# project2.net
KiCad netlist of a schematic drawn in EAGLE
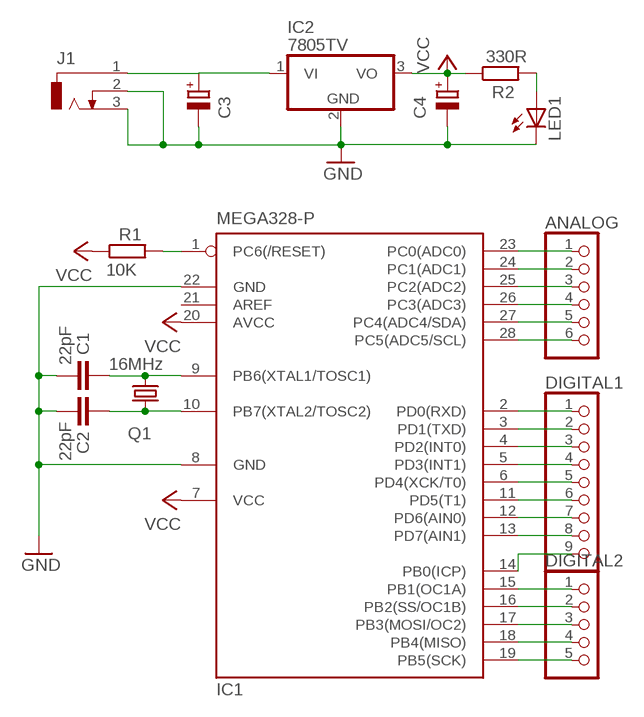
[diagram p0: schematic, sheet 1]

(export (version "E")
  (design (tool "Eeschema 10.0.6"))
  (components
    (comp (ref "ANALOG")
      (value "PINHD-1X6")
      (footprint "eagle-import:1X06")
      (libsource (lib "eagle-import") (part "PINHD-1X6"))
    )
    (comp (ref "C1")
      (value "22pF")
      (footprint "eagle-import:C025-024X044")
      (libsource (lib "eagle-import") (part "C-EU025-024X044"))
    )
    (comp (ref "C2")
      (value "22pF")
      (footprint "eagle-import:C025-024X044")
      (libsource (lib "eagle-import") (part "C-EU025-024X044"))
    )
    (comp (ref "C3")
      (value "CPOL-EUE2.5-6")
      (footprint "eagle-import:E2,5-6")
      (libsource (lib "eagle-import") (part "CPOL-EUE2.5-6"))
    )
    (comp (ref "C4")
      (value "CPOL-EUE2.5-6")
      (footprint "eagle-import:E2,5-6")
      (libsource (lib "eagle-import") (part "CPOL-EUE2.5-6"))
    )
    (comp (ref "DIGITAL1")
      (value "PINHD-1X9")
      (footprint "eagle-import:1X09")
      (libsource (lib "eagle-import") (part "PINHD-1X9"))
    )
    (comp (ref "DIGITAL2")
      (value "PINHD-1X5")
      (footprint "eagle-import:1X05")
      (libsource (lib "eagle-import") (part "PINHD-1X5"))
    )
    (comp (ref "IC1")
      (value "MEGA328-P")
      (footprint "eagle-import:DIL28-3")
      (libsource (lib "eagle-import") (part "MEGA8-P"))
    )
    (comp (ref "IC2")
      (value "7805TV")
      (footprint "eagle-import:TO220V")
      (libsource (lib "eagle-import") (part "78TV05"))
    )
    (comp (ref "J1")
      (value "DCJ0303")
      (footprint "eagle-import:DCJ0303")
      (libsource (lib "eagle-import") (part "DCJ0303"))
    )
    (comp (ref "LED1")
      (value "LED3MM")
      (footprint "eagle-import:LED3MM")
      (libsource (lib "eagle-import") (part "LED3MM"))
    )
    (comp (ref "Q1")
      (value "16MHz")
      (footprint "eagle-import:HC49U70")
      (libsource (lib "eagle-import") (part "CRYSTALHC49U70"))
    )
    (comp (ref "R1")
      (value "10K")
      (footprint "eagle-import:0207_10")
      (libsource (lib "eagle-import") (part "R-EU_0207/10"))
    )
    (comp (ref "R2")
      (value "330R")
      (footprint "eagle-import:0207_10")
      (libsource (lib "eagle-import") (part "R-EU_0207/10"))
    )
  )
  (nets
    (net (code "1") (name "GND") (class "Default")
      (node (ref "C1") (pin "2") (pinfunction "2_2") (pintype "passive"))
      (node (ref "C2") (pin "2") (pinfunction "2_2") (pintype "passive"))
      (node (ref "C3") (pin "-") (pinfunction "-_-") (pintype "passive"))
      (node (ref "C4") (pin "-") (pinfunction "-_-") (pintype "passive"))
      (node (ref "IC1") (pin "22") (pinfunction "GND_22") (pintype "power_in"))
      (node (ref "IC1") (pin "8") (pinfunction "GND_8") (pintype "power_in"))
      (node (ref "IC2") (pin "2") (pinfunction "GND_2") (pintype "passive"))
      (node (ref "J1") (pin "2") (pinfunction "2_2") (pintype "passive"))
      (node (ref "J1") (pin "3") (pinfunction "3_3") (pintype "passive"))
      (node (ref "LED1") (pin "K") (pinfunction "C_K") (pintype "passive"))
    )
    (net (code "2") (name "Net-(IC1-PB0(ICP))") (class "Default")
      (node (ref "DIGITAL1") (pin "9") (pinfunction "9_9") (pintype "passive"))
      (node (ref "IC1") (pin "14") (pinfunction "PB0(ICP)_14") (pintype "bidirectional"))
    )
    (net (code "3") (name "Net-(IC1-PB1(OC1A))") (class "Default")
      (node (ref "DIGITAL2") (pin "1") (pinfunction "1_1") (pintype "passive"))
      (node (ref "IC1") (pin "15") (pinfunction "PB1(OC1A)_15") (pintype "bidirectional"))
    )
    (net (code "4") (name "Net-(IC1-PB2(SS{slash}OC1B))") (class "Default")
      (node (ref "DIGITAL2") (pin "2") (pinfunction "2_2") (pintype "passive"))
      (node (ref "IC1") (pin "16") (pinfunction "PB2(SS/OC1B)_16") (pintype "bidirectional"))
    )
    (net (code "5") (name "Net-(IC1-PB3(MOSI{slash}OC2))") (class "Default")
      (node (ref "DIGITAL2") (pin "3") (pinfunction "3_3") (pintype "passive"))
      (node (ref "IC1") (pin "17") (pinfunction "PB3(MOSI/OC2)_17") (pintype "bidirectional"))
    )
    (net (code "6") (name "Net-(IC1-PB4(MISO))") (class "Default")
      (node (ref "DIGITAL2") (pin "4") (pinfunction "4_4") (pintype "passive"))
      (node (ref "IC1") (pin "18") (pinfunction "PB4(MISO)_18") (pintype "bidirectional"))
    )
    (net (code "7") (name "Net-(IC1-PB5(SCK))") (class "Default")
      (node (ref "DIGITAL2") (pin "5") (pinfunction "5_5") (pintype "passive"))
      (node (ref "IC1") (pin "19") (pinfunction "PB5(SCK)_19") (pintype "bidirectional"))
    )
    (net (code "8") (name "Net-(IC1-PB6(XTAL1{slash}TOSC1))") (class "Default")
      (node (ref "C1") (pin "1") (pinfunction "1_1") (pintype "passive"))
      (node (ref "IC1") (pin "9") (pinfunction "PB6(XTAL1/TOSC1)_9") (pintype "bidirectional"))
      (node (ref "Q1") (pin "1") (pinfunction "1_1") (pintype "passive"))
    )
    (net (code "9") (name "Net-(IC1-PB7(XTAL2{slash}TOSC2))") (class "Default")
      (node (ref "C2") (pin "1") (pinfunction "1_1") (pintype "passive"))
      (node (ref "IC1") (pin "10") (pinfunction "PB7(XTAL2/TOSC2)_10") (pintype "bidirectional"))
      (node (ref "Q1") (pin "2") (pinfunction "2_2") (pintype "passive"))
    )
    (net (code "10") (name "Net-(IC1-PC0(ADC0))") (class "Default")
      (node (ref "ANALOG") (pin "1") (pinfunction "1_1") (pintype "passive"))
      (node (ref "IC1") (pin "23") (pinfunction "PC0(ADC0)_23") (pintype "bidirectional"))
    )
    (net (code "11") (name "Net-(IC1-PC1(ADC1))") (class "Default")
      (node (ref "ANALOG") (pin "2") (pinfunction "2_2") (pintype "passive"))
      (node (ref "IC1") (pin "24") (pinfunction "PC1(ADC1)_24") (pintype "bidirectional"))
    )
    (net (code "12") (name "Net-(IC1-PC2(ADC2))") (class "Default")
      (node (ref "ANALOG") (pin "3") (pinfunction "3_3") (pintype "passive"))
      (node (ref "IC1") (pin "25") (pinfunction "PC2(ADC2)_25") (pintype "bidirectional"))
    )
    (net (code "13") (name "Net-(IC1-PC3(ADC3))") (class "Default")
      (node (ref "ANALOG") (pin "4") (pinfunction "4_4") (pintype "passive"))
      (node (ref "IC1") (pin "26") (pinfunction "PC3(ADC3)_26") (pintype "bidirectional"))
    )
    (net (code "14") (name "Net-(IC1-PC4(ADC4{slash}SDA))") (class "Default")
      (node (ref "ANALOG") (pin "5") (pinfunction "5_5") (pintype "passive"))
      (node (ref "IC1") (pin "27") (pinfunction "PC4(ADC4/SDA)_27") (pintype "bidirectional"))
    )
    (net (code "15") (name "Net-(IC1-PC5(ADC5{slash}SCL))") (class "Default")
      (node (ref "ANALOG") (pin "6") (pinfunction "6_6") (pintype "passive"))
      (node (ref "IC1") (pin "28") (pinfunction "PC5(ADC5/SCL)_28") (pintype "bidirectional"))
    )
    (net (code "16") (name "Net-(IC1-PC6({slash}RESET))") (class "Default")
      (node (ref "IC1") (pin "1") (pinfunction "PC6(/RESET)_1") (pintype "bidirectional"))
      (node (ref "R1") (pin "2") (pinfunction "2_2") (pintype "passive"))
    )
    (net (code "17") (name "Net-(IC1-PD0(RXD))") (class "Default")
      (node (ref "DIGITAL1") (pin "1") (pinfunction "1_1") (pintype "passive"))
      (node (ref "IC1") (pin "2") (pinfunction "PD0(RXD)_2") (pintype "bidirectional"))
    )
    (net (code "18") (name "Net-(IC1-PD1(TXD))") (class "Default")
      (node (ref "DIGITAL1") (pin "2") (pinfunction "2_2") (pintype "passive"))
      (node (ref "IC1") (pin "3") (pinfunction "PD1(TXD)_3") (pintype "bidirectional"))
    )
    (net (code "19") (name "Net-(IC1-PD2(INT0))") (class "Default")
      (node (ref "DIGITAL1") (pin "3") (pinfunction "3_3") (pintype "passive"))
      (node (ref "IC1") (pin "4") (pinfunction "PD2(INT0)_4") (pintype "bidirectional"))
    )
    (net (code "20") (name "Net-(IC1-PD3(INT1))") (class "Default")
      (node (ref "DIGITAL1") (pin "4") (pinfunction "4_4") (pintype "passive"))
      (node (ref "IC1") (pin "5") (pinfunction "PD3(INT1)_5") (pintype "bidirectional"))
    )
    (net (code "21") (name "Net-(IC1-PD4(XCK{slash}T0))") (class "Default")
      (node (ref "DIGITAL1") (pin "5") (pinfunction "5_5") (pintype "passive"))
      (node (ref "IC1") (pin "6") (pinfunction "PD4(XCK/T0)_6") (pintype "bidirectional"))
    )
    (net (code "22") (name "Net-(IC1-PD5(T1))") (class "Default")
      (node (ref "DIGITAL1") (pin "6") (pinfunction "6_6") (pintype "passive"))
      (node (ref "IC1") (pin "11") (pinfunction "PD5(T1)_11") (pintype "bidirectional"))
    )
    (net (code "23") (name "Net-(IC1-PD6(AIN0))") (class "Default")
      (node (ref "DIGITAL1") (pin "7") (pinfunction "7_7") (pintype "passive"))
      (node (ref "IC1") (pin "12") (pinfunction "PD6(AIN0)_12") (pintype "bidirectional"))
    )
    (net (code "24") (name "Net-(IC1-PD7(AIN1))") (class "Default")
      (node (ref "DIGITAL1") (pin "8") (pinfunction "8_8") (pintype "passive"))
      (node (ref "IC1") (pin "13") (pinfunction "PD7(AIN1)_13") (pintype "bidirectional"))
    )
    (net (code "25") (name "Net-(IC2-VI)") (class "Default")
      (node (ref "C3") (pin "+") (pinfunction "+_+") (pintype "passive"))
      (node (ref "IC2") (pin "1") (pinfunction "VI_1") (pintype "input"))
      (node (ref "J1") (pin "1") (pinfunction "1_1") (pintype "passive"))
    )
    (net (code "26") (name "Net-(LED1-PadA)") (class "Default")
      (node (ref "LED1") (pin "A") (pinfunction "A_A") (pintype "passive"))
      (node (ref "R2") (pin "2") (pinfunction "2_2") (pintype "passive"))
    )
    (net (code "27") (name "VCC") (class "Default")
      (node (ref "C4") (pin "+") (pinfunction "+_+") (pintype "passive"))
      (node (ref "IC1") (pin "20") (pinfunction "AVCC_20") (pintype "power_in"))
      (node (ref "IC1") (pin "7") (pinfunction "VCC_7") (pintype "power_in"))
      (node (ref "IC2") (pin "3") (pinfunction "VO_3") (pintype "passive"))
      (node (ref "R1") (pin "1") (pinfunction "1_1") (pintype "passive"))
      (node (ref "R2") (pin "1") (pinfunction "1_1") (pintype "passive"))
    )
    (net (code "28") (name "unconnected-(IC1-AREF-Pad21)") (class "Default")
      (node (ref "IC1") (pin "21") (pinfunction "AREF_21") (pintype "passive"))
    )
  )
)
